# sa_amp.net
KiCad netlist of a schematic drawn in EAGLE
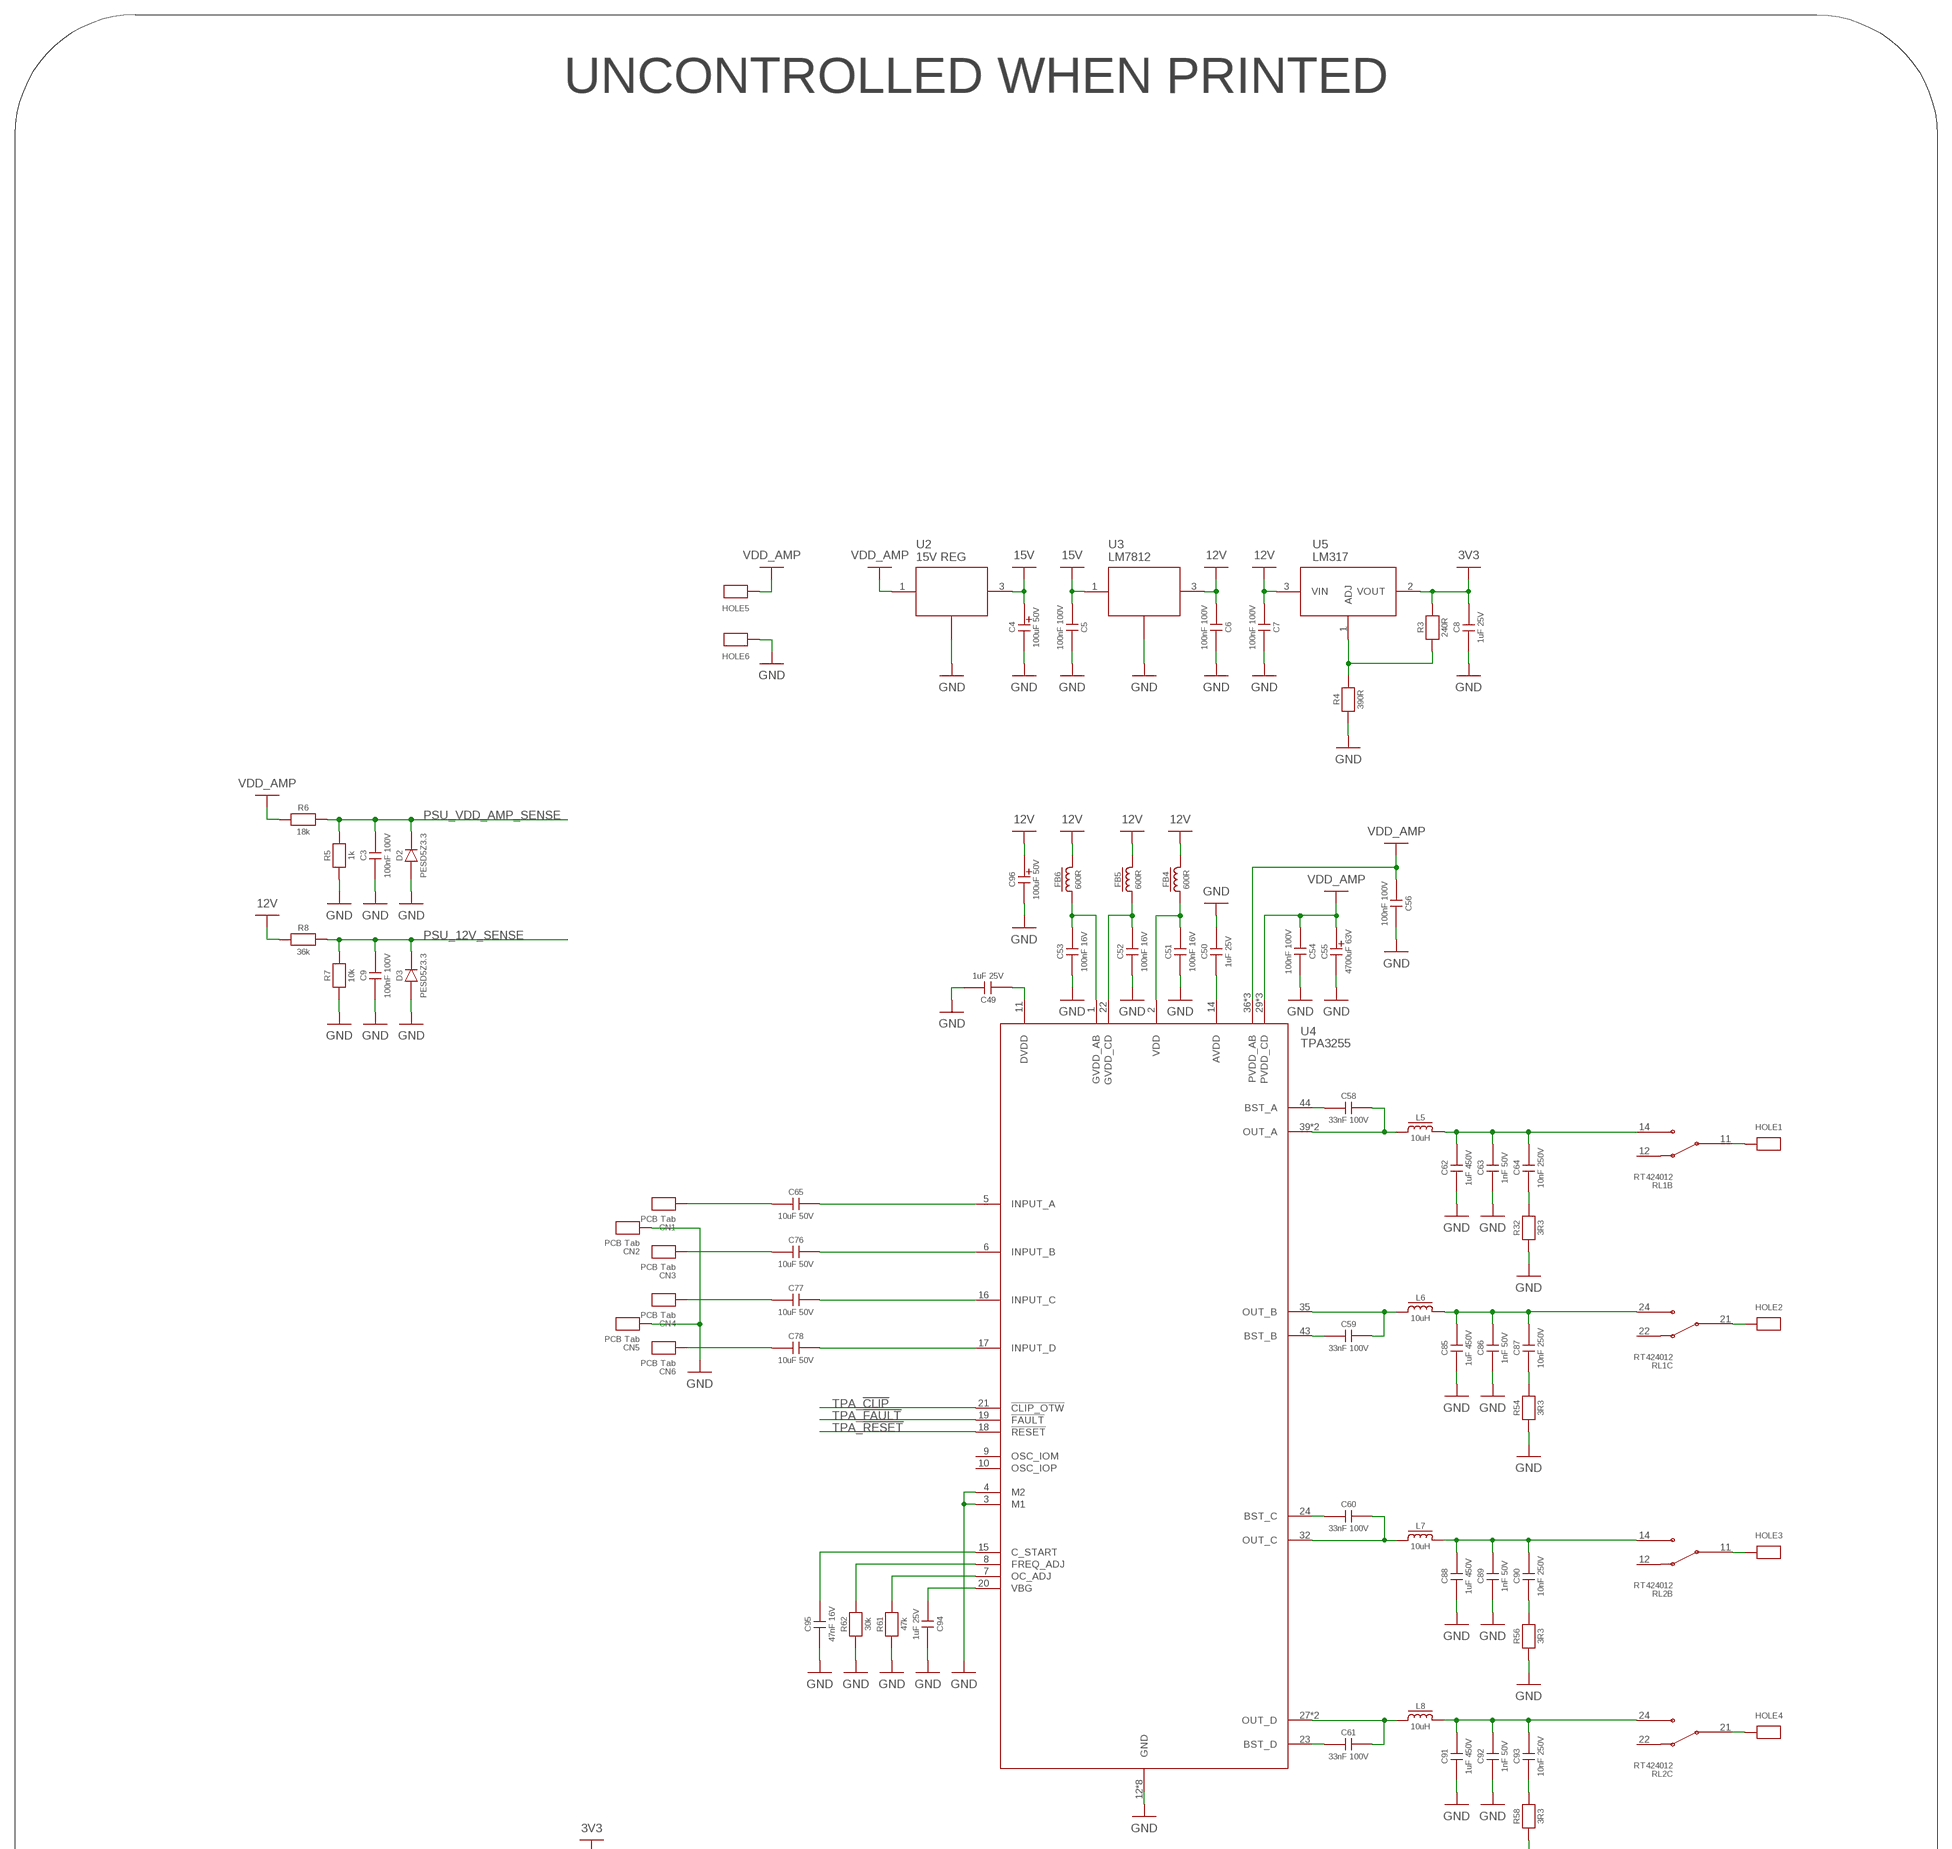
[diagram p0: schematic, sheet 1, part 1 of 2]
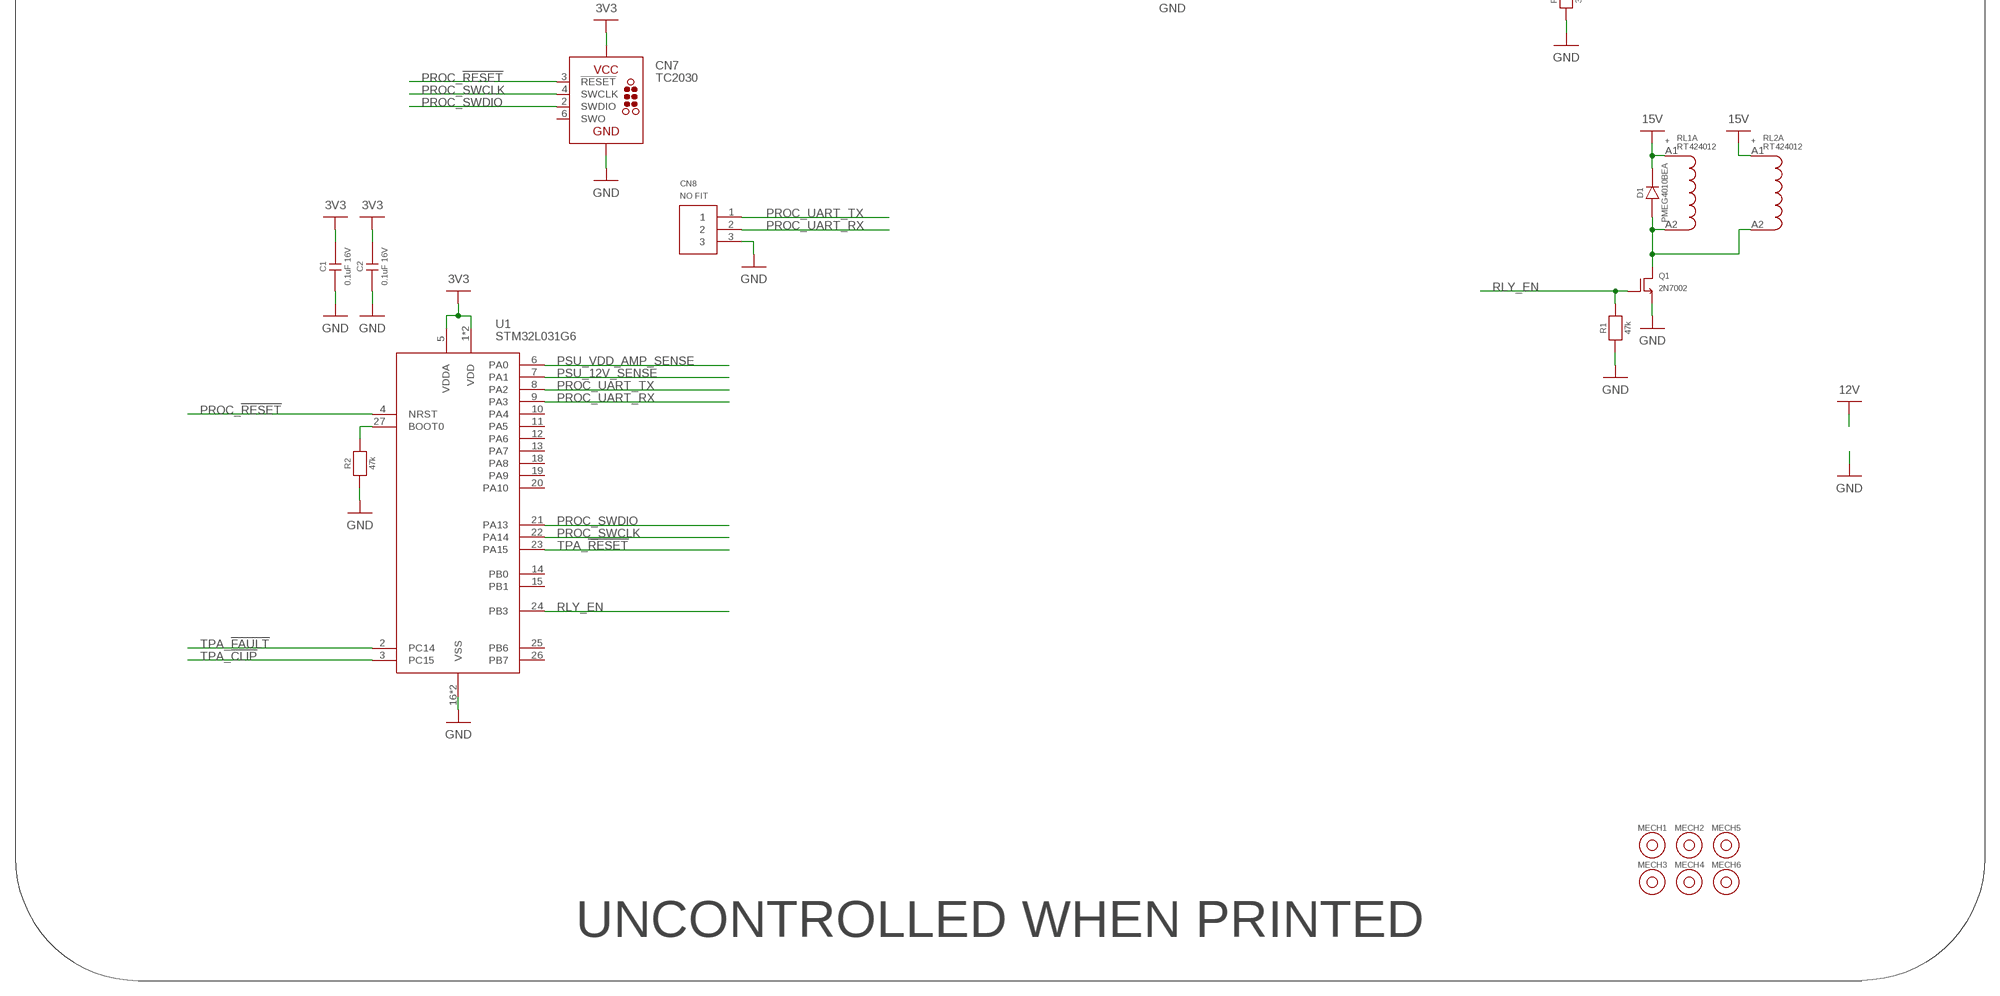
[diagram p1: schematic, sheet 1, part 2 of 2]

(export (version "E")
  (design (tool "Eeschema 10.0.6"))
  (components
    (comp (ref "C1")
      (value "0.1uF 16V")
      (footprint "eagle-import:0603")
      (fields
        (field (name "MANUFACTURER") "AVX Corporation")
        (field (name "TOLERANCE") "±10%")
        (field (name "VOLTAGE") "16V")
      )
      (libsource (lib "eagle-import") (part "0603YC104K4T4A"))
    )
    (comp (ref "C2")
      (value "0.1uF 16V")
      (footprint "eagle-import:0603")
      (fields
        (field (name "MANUFACTURER") "AVX Corporation")
        (field (name "TOLERANCE") "±10%")
        (field (name "VOLTAGE") "16V")
      )
      (libsource (lib "eagle-import") (part "0603YC104K4T4A"))
    )
    (comp (ref "C3")
      (value "100nF 100V")
      (footprint "eagle-import:0603")
      (libsource (lib "eagle-import") (part "06031C104KAT2A"))
    )
    (comp (ref "C4")
      (value "100uF 50V")
      (footprint "eagle-import:8MM_RADIAL_3.5MM_PITCH")
      (libsource (lib "eagle-import") (part "107CKR050M"))
    )
    (comp (ref "C5")
      (value "100nF 100V")
      (footprint "eagle-import:0603")
      (libsource (lib "eagle-import") (part "06031C104KAT2A"))
    )
    (comp (ref "C6")
      (value "100nF 100V")
      (footprint "eagle-import:0603")
      (libsource (lib "eagle-import") (part "06031C104KAT2A"))
    )
    (comp (ref "C7")
      (value "100nF 100V")
      (footprint "eagle-import:0603")
      (libsource (lib "eagle-import") (part "06031C104KAT2A"))
    )
    (comp (ref "C8")
      (value "1uF 25V")
      (footprint "eagle-import:0603")
      (libsource (lib "eagle-import") (part "CL10A105KA8NNNC"))
    )
    (comp (ref "C9")
      (value "100nF 100V")
      (footprint "eagle-import:0603")
      (libsource (lib "eagle-import") (part "06031C104KAT2A"))
    )
    (comp (ref "C49")
      (value "1uF 25V")
      (footprint "eagle-import:0603")
      (libsource (lib "eagle-import") (part "CL10A105KA8NNNC"))
    )
    (comp (ref "C50")
      (value "1uF 25V")
      (footprint "eagle-import:0603")
      (libsource (lib "eagle-import") (part "CL10A105KA8NNNC"))
    )
    (comp (ref "C51")
      (value "100nF 16V")
      (footprint "eagle-import:0603")
      (libsource (lib "eagle-import") (part "CL10B104KO8WPNC"))
    )
    (comp (ref "C52")
      (value "100nF 16V")
      (footprint "eagle-import:0603")
      (libsource (lib "eagle-import") (part "CL10B104KO8WPNC"))
    )
    (comp (ref "C53")
      (value "100nF 16V")
      (footprint "eagle-import:0603")
      (libsource (lib "eagle-import") (part "CL10B104KO8WPNC"))
    )
    (comp (ref "C54")
      (value "100nF 100V")
      (footprint "eagle-import:0603")
      (libsource (lib "eagle-import") (part "06031C104KAT2A"))
    )
    (comp (ref "C55")
      (value "4700uF 63V")
      (footprint "eagle-import:30MM_RADIAL_10MM_PITCH")
      (libsource (lib "eagle-import") (part "B41231C8478M000"))
    )
    (comp (ref "C56")
      (value "100nF 100V")
      (footprint "eagle-import:0603")
      (libsource (lib "eagle-import") (part "06031C104KAT2A"))
    )
    (comp (ref "C58")
      (value "33nF 100V")
      (footprint "eagle-import:0603")
      (libsource (lib "eagle-import") (part "C0603C333K1RACTU"))
    )
    (comp (ref "C59")
      (value "33nF 100V")
      (footprint "eagle-import:0603")
      (libsource (lib "eagle-import") (part "C0603C333K1RACTU"))
    )
    (comp (ref "C60")
      (value "33nF 100V")
      (footprint "eagle-import:0603")
      (libsource (lib "eagle-import") (part "C0603C333K1RACTU"))
    )
    (comp (ref "C61")
      (value "33nF 100V")
      (footprint "eagle-import:0603")
      (libsource (lib "eagle-import") (part "C0603C333K1RACTU"))
    )
    (comp (ref "C62")
      (value "1uF 450V")
      (footprint "eagle-import:7X17.5BOX")
      (libsource (lib "eagle-import") (part "ECWFE2W105K"))
    )
    (comp (ref "C63")
      (value "1nF 50V")
      (footprint "eagle-import:0603")
      (libsource (lib "eagle-import") (part "CL10B102KB8NNNC"))
    )
    (comp (ref "C64")
      (value "10nF 250V")
      (footprint "eagle-import:0603")
      (libsource (lib "eagle-import") (part "885342206006"))
    )
    (comp (ref "C65")
      (value "10uF 50V")
      (footprint "eagle-import:7.2X11BOX")
      (libsource (lib "eagle-import") (part "MKS2B051001N00JSSD"))
    )
    (comp (ref "C76")
      (value "10uF 50V")
      (footprint "eagle-import:7.2X11BOX")
      (libsource (lib "eagle-import") (part "MKS2B051001N00JSSD"))
    )
    (comp (ref "C77")
      (value "10uF 50V")
      (footprint "eagle-import:7.2X11BOX")
      (libsource (lib "eagle-import") (part "MKS2B051001N00JSSD"))
    )
    (comp (ref "C78")
      (value "10uF 50V")
      (footprint "eagle-import:7.2X11BOX")
      (libsource (lib "eagle-import") (part "MKS2B051001N00JSSD"))
    )
    (comp (ref "C85")
      (value "1uF 450V")
      (footprint "eagle-import:7X17.5BOX")
      (libsource (lib "eagle-import") (part "ECWFE2W105K"))
    )
    (comp (ref "C86")
      (value "1nF 50V")
      (footprint "eagle-import:0603")
      (libsource (lib "eagle-import") (part "CL10B102KB8NNNC"))
    )
    (comp (ref "C87")
      (value "10nF 250V")
      (footprint "eagle-import:0603")
      (libsource (lib "eagle-import") (part "885342206006"))
    )
    (comp (ref "C88")
      (value "1uF 450V")
      (footprint "eagle-import:7X17.5BOX")
      (libsource (lib "eagle-import") (part "ECWFE2W105K"))
    )
    (comp (ref "C89")
      (value "1nF 50V")
      (footprint "eagle-import:0603")
      (libsource (lib "eagle-import") (part "CL10B102KB8NNNC"))
    )
    (comp (ref "C90")
      (value "10nF 250V")
      (footprint "eagle-import:0603")
      (libsource (lib "eagle-import") (part "885342206006"))
    )
    (comp (ref "C91")
      (value "1uF 450V")
      (footprint "eagle-import:7X17.5BOX")
      (libsource (lib "eagle-import") (part "ECWFE2W105K"))
    )
    (comp (ref "C92")
      (value "1nF 50V")
      (footprint "eagle-import:0603")
      (libsource (lib "eagle-import") (part "CL10B102KB8NNNC"))
    )
    (comp (ref "C93")
      (value "10nF 250V")
      (footprint "eagle-import:0603")
      (libsource (lib "eagle-import") (part "885342206006"))
    )
    (comp (ref "C94")
      (value "1uF 25V")
      (footprint "eagle-import:0603")
      (libsource (lib "eagle-import") (part "CL10A105KA8NNNC"))
    )
    (comp (ref "C95")
      (value "47nF 16V")
      (footprint "eagle-import:0603")
      (libsource (lib "eagle-import") (part "CL10B473KO8NNNC"))
    )
    (comp (ref "C96")
      (value "100uF 50V")
      (footprint "eagle-import:8MM_RADIAL_3.5MM_PITCH")
      (libsource (lib "eagle-import") (part "107CKR050M"))
    )
    (comp (ref "CN1")
      (value "PCB Tab")
      (footprint "eagle-import:PCB_TAB_SMALL")
      (libsource (lib "eagle-import") (part "PCB_TAB_SMALL"))
    )
    (comp (ref "CN2")
      (value "PCB Tab")
      (footprint "eagle-import:PCB_TAB_SMALL")
      (libsource (lib "eagle-import") (part "PCB_TAB_SMALL"))
    )
    (comp (ref "CN3")
      (value "PCB Tab")
      (footprint "eagle-import:PCB_TAB_SMALL")
      (libsource (lib "eagle-import") (part "PCB_TAB_SMALL"))
    )
    (comp (ref "CN4")
      (value "PCB Tab")
      (footprint "eagle-import:PCB_TAB_SMALL")
      (libsource (lib "eagle-import") (part "PCB_TAB_SMALL"))
    )
    (comp (ref "CN5")
      (value "PCB Tab")
      (footprint "eagle-import:PCB_TAB_SMALL")
      (libsource (lib "eagle-import") (part "PCB_TAB_SMALL"))
    )
    (comp (ref "CN6")
      (value "PCB Tab")
      (footprint "eagle-import:PCB_TAB_SMALL")
      (libsource (lib "eagle-import") (part "PCB_TAB_SMALL"))
    )
    (comp (ref "CN7")
      (value "TC2030")
      (footprint "eagle-import:TC2030-MCP")
      (libsource (lib "eagle-import") (part "TC2030-MCP"))
    )
    (comp (ref "CN8")
      (value "NO FIT")
      (footprint "eagle-import:3PIN_HEADER")
      (libsource (lib "eagle-import") (part "1X3_HEADER"))
    )
    (comp (ref "D1")
      (value "PMEG4010BEA")
      (footprint "eagle-import:SOD-323")
      (libsource (lib "eagle-import") (part "PMEG4010BEA"))
    )
    (comp (ref "D2")
      (value "PESD5Z3.3")
      (footprint "eagle-import:SC-79")
      (libsource (lib "eagle-import") (part "PESD5Z3.3"))
    )
    (comp (ref "D3")
      (value "PESD5Z3.3")
      (footprint "eagle-import:SC-79")
      (libsource (lib "eagle-import") (part "PESD5Z3.3"))
    )
    (comp (ref "FB4")
      (value "600R")
      (footprint "eagle-import:0603")
      (libsource (lib "eagle-import") (part "742792651"))
    )
    (comp (ref "FB5")
      (value "600R")
      (footprint "eagle-import:0603")
      (libsource (lib "eagle-import") (part "742792651"))
    )
    (comp (ref "FB6")
      (value "600R")
      (footprint "eagle-import:0603")
      (libsource (lib "eagle-import") (part "742792651"))
    )
    (comp (ref "HOLE1")
      (value "PCB Tab")
      (footprint "eagle-import:PCB_TAB")
      (libsource (lib "eagle-import") (part "PCB_TAB"))
    )
    (comp (ref "HOLE2")
      (value "PCB Tab")
      (footprint "eagle-import:PCB_TAB")
      (libsource (lib "eagle-import") (part "PCB_TAB"))
    )
    (comp (ref "HOLE3")
      (value "PCB Tab")
      (footprint "eagle-import:PCB_TAB")
      (libsource (lib "eagle-import") (part "PCB_TAB"))
    )
    (comp (ref "HOLE4")
      (value "PCB Tab")
      (footprint "eagle-import:PCB_TAB")
      (libsource (lib "eagle-import") (part "PCB_TAB"))
    )
    (comp (ref "HOLE5")
      (value "PCB Tab")
      (footprint "eagle-import:PCB_TAB")
      (libsource (lib "eagle-import") (part "PCB_TAB"))
    )
    (comp (ref "HOLE6")
      (value "PCB Tab")
      (footprint "eagle-import:PCB_TAB")
      (libsource (lib "eagle-import") (part "PCB_TAB"))
    )
    (comp (ref "L5")
      (value "10uH")
      (footprint "eagle-import:SRP1265A")
      (libsource (lib "eagle-import") (part "SRP1265A-100M"))
    )
    (comp (ref "L6")
      (value "10uH")
      (footprint "eagle-import:SRP1265A")
      (libsource (lib "eagle-import") (part "SRP1265A-100M"))
    )
    (comp (ref "L7")
      (value "10uH")
      (footprint "eagle-import:SRP1265A")
      (libsource (lib "eagle-import") (part "SRP1265A-100M"))
    )
    (comp (ref "L8")
      (value "10uH")
      (footprint "eagle-import:SRP1265A")
      (libsource (lib "eagle-import") (part "SRP1265A-100M"))
    )
    (comp (ref "MECH1")
      (value "6mm x 3mm")
      (footprint "eagle-import:MOUNTHOLE_6X3")
      (libsource (lib "eagle-import") (part "MOUNTHOLE"))
    )
    (comp (ref "MECH2")
      (value "6mm x 3mm")
      (footprint "eagle-import:MOUNTHOLE_6X3")
      (libsource (lib "eagle-import") (part "MOUNTHOLE"))
    )
    (comp (ref "MECH3")
      (value "6mm x 3mm")
      (footprint "eagle-import:MOUNTHOLE_6X3")
      (libsource (lib "eagle-import") (part "MOUNTHOLE"))
    )
    (comp (ref "MECH4")
      (value "6mm x 3mm")
      (footprint "eagle-import:MOUNTHOLE_6X3")
      (libsource (lib "eagle-import") (part "MOUNTHOLE"))
    )
    (comp (ref "MECH5")
      (value "6mm x 3mm")
      (footprint "eagle-import:MOUNTHOLE_6X3")
      (libsource (lib "eagle-import") (part "MOUNTHOLE"))
    )
    (comp (ref "MECH6")
      (value "6mm x 3mm")
      (footprint "eagle-import:MOUNTHOLE_6X3")
      (libsource (lib "eagle-import") (part "MOUNTHOLE"))
    )
    (comp (ref "Q1")
      (value "2N7002")
      (footprint "eagle-import:SOT23-3")
      (libsource (lib "eagle-import") (part "2N7002P,215"))
    )
    (comp (ref "R1")
      (value "47k")
      (footprint "eagle-import:0603")
      (libsource (lib "eagle-import") (part "ERJ3EKF4702V"))
    )
    (comp (ref "R2")
      (value "47k")
      (footprint "eagle-import:0603")
      (libsource (lib "eagle-import") (part "ERJ3EKF4702V"))
    )
    (comp (ref "R3")
      (value "240R")
      (footprint "eagle-import:0603")
      (fields
        (field (name "MANUFACTURER") "Vishay Dale")
        (field (name "POWER") "0.1W, 1/10W")
        (field (name "TOLERANCE") "±1%")
      )
      (libsource (lib "eagle-import") (part "CRCW0603240RFKEA"))
    )
    (comp (ref "R4")
      (value "390R")
      (footprint "eagle-import:0603")
      (fields
        (field (name "MANUFACTURER") "Vishay Dale")
        (field (name "POWER") "0.1W, 1/10W")
        (field (name "TOLERANCE") "±1%")
      )
      (libsource (lib "eagle-import") (part "CRCW0603390RFKEA"))
    )
    (comp (ref "R5")
      (value "1k")
      (footprint "eagle-import:0603")
      (fields
        (field (name "MANUFACTURER") "Vishay Dale")
        (field (name "POWER") "0.1W, 1/10W")
        (field (name "TOLERANCE") "±1%")
      )
      (libsource (lib "eagle-import") (part "CRCW06031K00FKEB"))
    )
    (comp (ref "R6")
      (value "18k")
      (footprint "eagle-import:0603")
      (fields
        (field (name "MANUFACTURER") "Vishay Dale")
        (field (name "POWER") "0.1W, 1/10W")
        (field (name "TOLERANCE") "±1%")
      )
      (libsource (lib "eagle-import") (part "CRCW060318K0FKEA"))
    )
    (comp (ref "R7")
      (value "10k")
      (footprint "eagle-import:0603")
      (fields
        (field (name "MANUFACTURER") "Vishay Dale")
        (field (name "POWER") "0.1W, 1/10W")
        (field (name "TOLERANCE") "±1%")
      )
      (libsource (lib "eagle-import") (part "CRCW060310K0FKTA"))
    )
    (comp (ref "R8")
      (value "36k")
      (footprint "eagle-import:0603")
      (fields
        (field (name "MANUFACTURER") "Vishay Dale")
        (field (name "POWER") "0.1W, 1/10W")
        (field (name "TOLERANCE") "±1%")
      )
      (libsource (lib "eagle-import") (part "CRCW060336K0FKEA"))
    )
    (comp (ref "R32")
      (value "3R3")
      (footprint "eagle-import:2512")
      (libsource (lib "eagle-import") (part "RL73H3AR10FTDF"))
    )
    (comp (ref "R54")
      (value "3R3")
      (footprint "eagle-import:2512")
      (libsource (lib "eagle-import") (part "RL73H3AR10FTDF"))
    )
    (comp (ref "R56")
      (value "3R3")
      (footprint "eagle-import:2512")
      (libsource (lib "eagle-import") (part "RL73H3AR10FTDF"))
    )
    (comp (ref "R58")
      (value "3R3")
      (footprint "eagle-import:2512")
      (libsource (lib "eagle-import") (part "RL73H3AR10FTDF"))
    )
    (comp (ref "R61")
      (value "47k")
      (footprint "eagle-import:0603")
      (libsource (lib "eagle-import") (part "ERJ3EKF4702V"))
    )
    (comp (ref "R62")
      (value "30k")
      (footprint "eagle-import:0603")
      (libsource (lib "eagle-import") (part "ERJ3EKF3002V"))
    )
    (comp (ref "RL1")
      (value "RT424012")
      (footprint "eagle-import:30MMDPDTRELAY")
      (libsource (lib "eagle-import") (part "RT424012"))
    )
    (comp (ref "RL2")
      (value "RT424012")
      (footprint "eagle-import:30MMDPDTRELAY")
      (libsource (lib "eagle-import") (part "RT424012"))
    )
    (comp (ref "U1")
      (value "STM32L031G6")
      (footprint "eagle-import:UFQPN28")
      (libsource (lib "eagle-import") (part "STM32L031G6"))
    )
    (comp (ref "U2")
      (value "15V REG")
      (footprint "eagle-import:SRH05")
      (libsource (lib "eagle-import") (part "SRH05S15"))
    )
    (comp (ref "U3")
      (value "LM7812")
      (footprint "eagle-import:TO220")
      (libsource (lib "eagle-import") (part "78CTG12"))
    )
    (comp (ref "U4")
      (value "TPA3255")
      (footprint "eagle-import:HTSSOP44")
      (libsource (lib "eagle-import") (part "TPA3255"))
    )
    (comp (ref "U5")
      (value "LM317")
      (footprint "eagle-import:SOT89")
      (libsource (lib "eagle-import") (part "LM317LCPK"))
    )
  )
  (nets
    (net (code "1") (name "/PROC_SWCLK") (class "Default")
      (node (ref "CN7") (pin "4") (pinfunction "SWCLK_4") (pintype "power_in"))
      (node (ref "U1") (pin "22") (pinfunction "PA14_22") (pintype "bidirectional"))
    )
    (net (code "2") (name "/PROC_SWDIO") (class "Default")
      (node (ref "CN7") (pin "2") (pinfunction "SWDIO_2") (pintype "bidirectional"))
      (node (ref "U1") (pin "21") (pinfunction "PA13_21") (pintype "bidirectional"))
    )
    (net (code "3") (name "/PROC_UART_RX") (class "Default")
      (node (ref "CN8") (pin "2") (pinfunction "2_2") (pintype "bidirectional"))
      (node (ref "U1") (pin "9") (pinfunction "PA3_9") (pintype "bidirectional"))
    )
    (net (code "4") (name "/PROC_UART_TX") (class "Default")
      (node (ref "CN8") (pin "1") (pinfunction "1_1") (pintype "bidirectional"))
      (node (ref "U1") (pin "8") (pinfunction "PA2_8") (pintype "bidirectional"))
    )
    (net (code "5") (name "/PROC_~{RESET}") (class "Default")
      (node (ref "CN7") (pin "3") (pinfunction "~{RESET}_3") (pintype "power_in"))
      (node (ref "U1") (pin "4") (pinfunction "NRST_4") (pintype "bidirectional"))
    )
    (net (code "6") (name "/PSU_12V_SENSE") (class "Default")
      (node (ref "C9") (pin "1") (pinfunction "1_1") (pintype "bidirectional"))
      (node (ref "D3") (pin "K") (pinfunction "K_K") (pintype "bidirectional"))
      (node (ref "R7") (pin "2") (pinfunction "2_2") (pintype "bidirectional"))
      (node (ref "R8") (pin "2") (pinfunction "2_2") (pintype "bidirectional"))
      (node (ref "U1") (pin "7") (pinfunction "PA1_7") (pintype "bidirectional"))
    )
    (net (code "7") (name "/PSU_VDD_AMP_SENSE") (class "Default")
      (node (ref "C3") (pin "1") (pinfunction "1_1") (pintype "bidirectional"))
      (node (ref "D2") (pin "K") (pinfunction "K_K") (pintype "bidirectional"))
      (node (ref "R5") (pin "2") (pinfunction "2_2") (pintype "bidirectional"))
      (node (ref "R6") (pin "2") (pinfunction "2_2") (pintype "bidirectional"))
      (node (ref "U1") (pin "6") (pinfunction "PA0_6") (pintype "bidirectional"))
    )
    (net (code "8") (name "/RLY_EN") (class "Default")
      (node (ref "Q1") (pin "1") (pinfunction "G_1") (pintype "bidirectional"))
      (node (ref "R1") (pin "2") (pinfunction "2_2") (pintype "bidirectional"))
      (node (ref "U1") (pin "24") (pinfunction "PB3_24") (pintype "bidirectional"))
    )
    (net (code "9") (name "/TPA_~{CLIP}") (class "Default")
      (node (ref "U1") (pin "3") (pinfunction "PC15_3") (pintype "bidirectional"))
      (node (ref "U4") (pin "21") (pinfunction "~{CLIP_OTW}_21") (pintype "bidirectional"))
    )
    (net (code "10") (name "/TPA_~{FAULT}") (class "Default")
      (node (ref "U1") (pin "2") (pinfunction "PC14_2") (pintype "bidirectional"))
      (node (ref "U4") (pin "19") (pinfunction "~{FAULT}_19") (pintype "bidirectional"))
    )
    (net (code "11") (name "/TPA_~{RESET}") (class "Default")
      (node (ref "U1") (pin "23") (pinfunction "PA15_23") (pintype "bidirectional"))
      (node (ref "U4") (pin "18") (pinfunction "~{RESET}_18") (pintype "bidirectional"))
    )
    (net (code "12") (name "3V3") (class "Default")
      (node (ref "C1") (pin "2") (pinfunction "2_2") (pintype "bidirectional"))
      (node (ref "C2") (pin "2") (pinfunction "2_2") (pintype "bidirectional"))
      (node (ref "C8") (pin "2") (pinfunction "2_2") (pintype "bidirectional"))
      (node (ref "CN7") (pin "1") (pinfunction "VCC_1") (pintype "passive"))
      (node (ref "R3") (pin "2") (pinfunction "2_2") (pintype "bidirectional"))
      (node (ref "U1") (pin "1") (pinfunction "VDD_1") (pintype "bidirectional"))
      (node (ref "U1") (pin "17") (pinfunction "VDD_17") (pintype "bidirectional"))
      (node (ref "U1") (pin "5") (pinfunction "VDDA_5") (pintype "bidirectional"))
      (node (ref "U5") (pin "2") (pinfunction "VOUT_2") (pintype "bidirectional"))
    )
    (net (code "13") (name "12V") (class "Default")
      (node (ref "C6") (pin "1") (pinfunction "1_1") (pintype "bidirectional"))
      (node (ref "C7") (pin "1") (pinfunction "1_1") (pintype "bidirectional"))
      (node (ref "C96") (pin "P") (pinfunction "A_P") (pintype "bidirectional"))
      (node (ref "FB4") (pin "2") (pinfunction "2_2") (pintype "bidirectional"))
      (node (ref "FB5") (pin "2") (pinfunction "2_2") (pintype "bidirectional"))
      (node (ref "FB6") (pin "2") (pinfunction "2_2") (pintype "bidirectional"))
      (node (ref "R8") (pin "1") (pinfunction "1_1") (pintype "bidirectional"))
      (node (ref "U3") (pin "3") (pinfunction "VOUT_3") (pintype "bidirectional"))
      (node (ref "U5") (pin "3") (pinfunction "VIN_3") (pintype "bidirectional"))
    )
    (net (code "14") (name "15V") (class "Default")
      (node (ref "C4") (pin "P") (pinfunction "A_P") (pintype "bidirectional"))
      (node (ref "C5") (pin "1") (pinfunction "1_1") (pintype "bidirectional"))
      (node (ref "D1") (pin "K") (pinfunction "K_K") (pintype "bidirectional"))
      (node (ref "RL1") (pin "A1") (pinfunction "A1_A1") (pintype "bidirectional"))
      (node (ref "RL2") (pin "A1") (pinfunction "A1_A1") (pintype "bidirectional"))
      (node (ref "U2") (pin "3") (pinfunction "VOUT_3") (pintype "bidirectional"))
      (node (ref "U3") (pin "1") (pinfunction "VIN_1") (pintype "bidirectional"))
    )
    (net (code "15") (name "GND") (class "Default")
      (node (ref "C1") (pin "1") (pinfunction "1_1") (pintype "bidirectional"))
      (node (ref "C2") (pin "1") (pinfunction "1_1") (pintype "bidirectional"))
      (node (ref "C3") (pin "2") (pinfunction "2_2") (pintype "bidirectional"))
      (node (ref "C4") (pin "N") (pinfunction "K_N") (pintype "bidirectional"))
      (node (ref "C49") (pin "2") (pinfunction "2_2") (pintype "bidirectional"))
      (node (ref "C5") (pin "2") (pinfunction "2_2") (pintype "bidirectional"))
      (node (ref "C50") (pin "2") (pinfunction "2_2") (pintype "bidirectional"))
      (node (ref "C51") (pin "1") (pinfunction "1_1") (pintype "bidirectional"))
      (node (ref "C52") (pin "1") (pinfunction "1_1") (pintype "bidirectional"))
      (node (ref "C53") (pin "1") (pinfunction "1_1") (pintype "bidirectional"))
      (node (ref "C54") (pin "2") (pinfunction "2_2") (pintype "bidirectional"))
      (node (ref "C55") (pin "1") (pinfunction "K_1") (pintype "bidirectional"))
      (node (ref "C56") (pin "2") (pinfunction "2_2") (pintype "bidirectional"))
      (node (ref "C6") (pin "2") (pinfunction "2_2") (pintype "bidirectional"))
      (node (ref "C62") (pin "1") (pinfunction "1_1") (pintype "bidirectional"))
      (node (ref "C63") (pin "1") (pinfunction "1_1") (pintype "bidirectional"))
      (node (ref "C7") (pin "2") (pinfunction "2_2") (pintype "bidirectional"))
      (node (ref "C8") (pin "1") (pinfunction "1_1") (pintype "bidirectional"))
      (node (ref "C85") (pin "1") (pinfunction "1_1") (pintype "bidirectional"))
      (node (ref "C86") (pin "1") (pinfunction "1_1") (pintype "bidirectional"))
      (node (ref "C88") (pin "1") (pinfunction "1_1") (pintype "bidirectional"))
      (node (ref "C89") (pin "1") (pinfunction "1_1") (pintype "bidirectional"))
      (node (ref "C9") (pin "2") (pinfunction "2_2") (pintype "bidirectional"))
      (node (ref "C91") (pin "1") (pinfunction "1_1") (pintype "bidirectional"))
      (node (ref "C92") (pin "1") (pinfunction "1_1") (pintype "bidirectional"))
      (node (ref "C94") (pin "2") (pinfunction "2_2") (pintype "bidirectional"))
      (node (ref "C95") (pin "1") (pinfunction "1_1") (pintype "bidirectional"))
      (node (ref "C96") (pin "N") (pinfunction "K_N") (pintype "bidirectional"))
      (node (ref "CN2") (pin "1") (pinfunction "1_1") (pintype "bidirectional"))
      (node (ref "CN5") (pin "1") (pinfunction "1_1") (pintype "bidirectional"))
      (node (ref "CN7") (pin "5") (pinfunction "GND_5") (pintype "bidirectional"))
      (node (ref "CN8") (pin "3") (pinfunction "3_3") (pintype "bidirectional"))
      (node (ref "D2") (pin "A") (pinfunction "A_A") (pintype "bidirectional"))
      (node (ref "D3") (pin "A") (pinfunction "A_A") (pintype "bidirectional"))
      (node (ref "HOLE6") (pin "1") (pinfunction "1_1") (pintype "bidirectional"))
      (node (ref "Q1") (pin "3") (pinfunction "S_3") (pintype "bidirectional"))
      (node (ref "R1") (pin "1") (pinfunction "1_1") (pintype "bidirectional"))
      (node (ref "R2") (pin "1") (pinfunction "1_1") (pintype "bidirectional"))
      (node (ref "R32") (pin "1") (pinfunction "1_1") (pintype "bidirectional"))
      (node (ref "R4") (pin "1") (pinfunction "1_1") (pintype "bidirectional"))
      (node (ref "R5") (pin "1") (pinfunction "1_1") (pintype "bidirectional"))
      (node (ref "R54") (pin "1") (pinfunction "1_1") (pintype "bidirectional"))
      (node (ref "R56") (pin "1") (pinfunction "1_1") (pintype "bidirectional"))
      (node (ref "R58") (pin "1") (pinfunction "1_1") (pintype "bidirectional"))
      (node (ref "R61") (pin "1") (pinfunction "1_1") (pintype "bidirectional"))
      (node (ref "R62") (pin "1") (pinfunction "1_1") (pintype "bidirectional"))
      (node (ref "R7") (pin "1") (pinfunction "1_1") (pintype "bidirectional"))
      (node (ref "U1") (pin "16") (pinfunction "VSS_16") (pintype "bidirectional"))
      (node (ref "U1") (pin "28") (pinfunction "VSS_28") (pintype "bidirectional"))
      (node (ref "U2") (pin "2") (pinfunction "GND_2") (pintype "bidirectional"))
      (node (ref "U3") (pin "2") (pinfunction "GND_2") (pintype "bidirectional"))
      (node (ref "U4") (pin "12") (pinfunction "GND_12") (pintype "bidirectional"))
      (node (ref "U4") (pin "13") (pinfunction "GND_13") (pintype "bidirectional"))
      (node (ref "U4") (pin "25") (pinfunction "GND_25") (pintype "bidirectional"))
      (node (ref "U4") (pin "26") (pinfunction "GND_26") (pintype "bidirectional"))
      (node (ref "U4") (pin "3") (pinfunction "M1_3") (pintype "bidirectional"))
      (node (ref "U4") (pin "33") (pinfunction "GND_33") (pintype "bidirectional"))
      (node (ref "U4") (pin "34") (pinfunction "GND_34") (pintype "bidirectional"))
      (node (ref "U4") (pin "4") (pinfunction "M2_4") (pintype "bidirectional"))
      (node (ref "U4") (pin "41") (pinfunction "GND_41") (pintype "bidirectional"))
      (node (ref "U4") (pin "42") (pinfunction "GND_42") (pintype "bidirectional"))
    )
    (net (code "16") (name "Net-(C58-Pad2)") (class "Default")
      (node (ref "C58") (pin "2") (pinfunction "2_2") (pintype "bidirectional"))
      (node (ref "L5") (pin "1") (pinfunction "1_1") (pintype "bidirectional"))
      (node (ref "U4") (pin "39") (pinfunction "OUT_A_39") (pintype "bidirectional"))
      (node (ref "U4") (pin "40") (pinfunction "OUT_A_40") (pintype "bidirectional"))
    )
    (net (code "17") (name "Net-(C61-Pad2)") (class "Default")
      (node (ref "C61") (pin "2") (pinfunction "2_2") (pintype "bidirectional"))
      (node (ref "L8") (pin "1") (pinfunction "1_1") (pintype "bidirectional"))
      (node (ref "U4") (pin "27") (pinfunction "OUT_D_27") (pintype "bidirectional"))
      (node (ref "U4") (pin "28") (pinfunction "OUT_D_28") (pintype "bidirectional"))
    )
    (net (code "18") (name "Net-(C64-Pad1)") (class "Default")
      (node (ref "C64") (pin "1") (pinfunction "1_1") (pintype "bidirectional"))
      (node (ref "R32") (pin "2") (pinfunction "2_2") (pintype "bidirectional"))
    )
    (net (code "19") (name "Net-(C65-Pad1)") (class "Default")
      (node (ref "C65") (pin "1") (pinfunction "1_1") (pintype "bidirectional"))
      (node (ref "CN1") (pin "1") (pinfunction "1_1") (pintype "bidirectional"))
    )
    (net (code "20") (name "Net-(C76-Pad1)") (class "Default")
      (node (ref "C76") (pin "1") (pinfunction "1_1") (pintype "bidirectional"))
      (node (ref "CN3") (pin "1") (pinfunction "1_1") (pintype "bidirectional"))
    )
    (net (code "21") (name "Net-(C77-Pad1)") (class "Default")
      (node (ref "C77") (pin "1") (pinfunction "1_1") (pintype "bidirectional"))
      (node (ref "CN4") (pin "1") (pinfunction "1_1") (pintype "bidirectional"))
    )
    (net (code "22") (name "Net-(C78-Pad1)") (class "Default")
      (node (ref "C78") (pin "1") (pinfunction "1_1") (pintype "bidirectional"))
      (node (ref "CN6") (pin "1") (pinfunction "1_1") (pintype "bidirectional"))
    )
    (net (code "23") (name "Net-(C87-Pad1)") (class "Default")
      (node (ref "C87") (pin "1") (pinfunction "1_1") (pintype "bidirectional"))
      (node (ref "R54") (pin "2") (pinfunction "2_2") (pintype "bidirectional"))
    )
    (net (code "24") (name "Net-(C90-Pad1)") (class "Default")
      (node (ref "C90") (pin "1") (pinfunction "1_1") (pintype "bidirectional"))
      (node (ref "R56") (pin "2") (pinfunction "2_2") (pintype "bidirectional"))
    )
    (net (code "25") (name "Net-(C93-Pad1)") (class "Default")
      (node (ref "C93") (pin "1") (pinfunction "1_1") (pintype "bidirectional"))
      (node (ref "R58") (pin "2") (pinfunction "2_2") (pintype "bidirectional"))
    )
    (net (code "26") (name "Net-(Q1-D)") (class "Default")
      (node (ref "D1") (pin "A") (pinfunction "A_A") (pintype "bidirectional"))
      (node (ref "Q1") (pin "2") (pinfunction "D_2") (pintype "bidirectional"))
      (node (ref "RL1") (pin "A2") (pinfunction "A2_A2") (pintype "bidirectional"))
      (node (ref "RL2") (pin "A2") (pinfunction "A2_A2") (pintype "bidirectional"))
    )
    (net (code "27") (name "Net-(RL1B-1)") (class "Default")
      (node (ref "HOLE1") (pin "1") (pinfunction "1_1") (pintype "bidirectional"))
      (node (ref "RL1") (pin "11") (pinfunction "1_11") (pintype "bidirectional"))
    )
    (net (code "28") (name "Net-(RL1B-3)") (class "Default")
      (node (ref "C62") (pin "2") (pinfunction "2_2") (pintype "bidirectional"))
      (node (ref "C63") (pin "2") (pinfunction "2_2") (pintype "bidirectional"))
      (node (ref "C64") (pin "2") (pinfunction "2_2") (pintype "bidirectional"))
      (node (ref "L5") (pin "2") (pinfunction "2_2") (pintype "bidirectional"))
      (node (ref "RL1") (pin "14") (pinfunction "3_14") (pintype "bidirectional"))
    )
    (net (code "29") (name "Net-(RL1C-1)") (class "Default")
      (node (ref "HOLE2") (pin "1") (pinfunction "1_1") (pintype "bidirectional"))
      (node (ref "RL1") (pin "21") (pinfunction "1_21") (pintype "bidirectional"))
    )
    (net (code "30") (name "Net-(RL1C-3)") (class "Default")
      (node (ref "C85") (pin "2") (pinfunction "2_2") (pintype "bidirectional"))
      (node (ref "C86") (pin "2") (pinfunction "2_2") (pintype "bidirectional"))
      (node (ref "C87") (pin "2") (pinfunction "2_2") (pintype "bidirectional"))
      (node (ref "L6") (pin "2") (pinfunction "2_2") (pintype "bidirectional"))
      (node (ref "RL1") (pin "24") (pinfunction "3_24") (pintype "bidirectional"))
    )
    (net (code "31") (name "Net-(RL2B-1)") (class "Default")
      (node (ref "HOLE3") (pin "1") (pinfunction "1_1") (pintype "bidirectional"))
      (node (ref "RL2") (pin "11") (pinfunction "1_11") (pintype "bidirectional"))
    )
    (net (code "32") (name "Net-(RL2B-3)") (class "Default")
      (node (ref "C88") (pin "2") (pinfunction "2_2") (pintype "bidirectional"))
      (node (ref "C89") (pin "2") (pinfunction "2_2") (pintype "bidirectional"))
      (node (ref "C90") (pin "2") (pinfunction "2_2") (pintype "bidirectional"))
      (node (ref "L7") (pin "2") (pinfunction "2_2") (pintype "bidirectional"))
      (node (ref "RL2") (pin "14") (pinfunction "3_14") (pintype "bidirectional"))
    )
    (net (code "33") (name "Net-(RL2C-1)") (class "Default")
      (node (ref "HOLE4") (pin "1") (pinfunction "1_1") (pintype "bidirectional"))
      (node (ref "RL2") (pin "21") (pinfunction "1_21") (pintype "bidirectional"))
    )
    (net (code "34") (name "Net-(RL2C-3)") (class "Default")
      (node (ref "C91") (pin "2") (pinfunction "2_2") (pintype "bidirectional"))
      (node (ref "C92") (pin "2") (pinfunction "2_2") (pintype "bidirectional"))
      (node (ref "C93") (pin "2") (pinfunction "2_2") (pintype "bidirectional"))
      (node (ref "L8") (pin "2") (pinfunction "2_2") (pintype "bidirectional"))
      (node (ref "RL2") (pin "24") (pinfunction "3_24") (pintype "bidirectional"))
    )
    (net (code "35") (name "Net-(U1-BOOT0)") (class "Default")
      (node (ref "R2") (pin "2") (pinfunction "2_2") (pintype "bidirectional"))
      (node (ref "U1") (pin "27") (pinfunction "BOOT0_27") (pintype "bidirectional"))
    )
    (net (code "36") (name "Net-(U4-AVDD)") (class "Default")
      (node (ref "C50") (pin "1") (pinfunction "1_1") (pintype "bidirectional"))
      (node (ref "U4") (pin "14") (pinfunction "AVDD_14") (pintype "bidirectional"))
    )
    (net (code "37") (name "Net-(U4-BST_A)") (class "Default")
      (node (ref "C58") (pin "1") (pinfunction "1_1") (pintype "bidirectional"))
      (node (ref "U4") (pin "44") (pinfunction "BST_A_44") (pintype "bidirectional"))
    )
    (net (code "38") (name "Net-(U4-BST_B)") (class "Default")
      (node (ref "C59") (pin "1") (pinfunction "1_1") (pintype "bidirectional"))
      (node (ref "U4") (pin "43") (pinfunction "BST_B_43") (pintype "bidirectional"))
    )
    (net (code "39") (name "Net-(U4-BST_C)") (class "Default")
      (node (ref "C60") (pin "1") (pinfunction "1_1") (pintype "bidirectional"))
      (node (ref "U4") (pin "24") (pinfunction "BST_C_24") (pintype "bidirectional"))
    )
    (net (code "40") (name "Net-(U4-BST_D)") (class "Default")
      (node (ref "C61") (pin "1") (pinfunction "1_1") (pintype "bidirectional"))
      (node (ref "U4") (pin "23") (pinfunction "BST_D_23") (pintype "bidirectional"))
    )
    (net (code "41") (name "Net-(U4-C_START)") (class "Default")
      (node (ref "C95") (pin "2") (pinfunction "2_2") (pintype "bidirectional"))
      (node (ref "U4") (pin "15") (pinfunction "C_START_15") (pintype "bidirectional"))
    )
    (net (code "42") (name "Net-(U4-DVDD)") (class "Default")
      (node (ref "C49") (pin "1") (pinfunction "1_1") (pintype "bidirectional"))
      (node (ref "U4") (pin "11") (pinfunction "DVDD_11") (pintype "bidirectional"))
    )
    (net (code "43") (name "Net-(U4-FREQ_ADJ)") (class "Default")
      (node (ref "R62") (pin "2") (pinfunction "2_2") (pintype "bidirectional"))
      (node (ref "U4") (pin "8") (pinfunction "FREQ_ADJ_8") (pintype "bidirectional"))
    )
    (net (code "44") (name "Net-(U4-GVDD_AB)") (class "Default")
      (node (ref "C53") (pin "2") (pinfunction "2_2") (pintype "bidirectional"))
      (node (ref "FB6") (pin "1") (pinfunction "1_1") (pintype "bidirectional"))
      (node (ref "U4") (pin "1") (pinfunction "GVDD_AB_1") (pintype "bidirectional"))
    )
    (net (code "45") (name "Net-(U4-GVDD_CD)") (class "Default")
      (node (ref "C52") (pin "2") (pinfunction "2_2") (pintype "bidirectional"))
      (node (ref "FB5") (pin "1") (pinfunction "1_1") (pintype "bidirectional"))
      (node (ref "U4") (pin "22") (pinfunction "GVDD_CD_22") (pintype "bidirectional"))
    )
    (net (code "46") (name "Net-(U4-INPUT_A)") (class "Default")
      (node (ref "C65") (pin "2") (pinfunction "2_2") (pintype "bidirectional"))
      (node (ref "U4") (pin "5") (pinfunction "INPUT_A_5") (pintype "bidirectional"))
    )
    (net (code "47") (name "Net-(U4-INPUT_B)") (class "Default")
      (node (ref "C76") (pin "2") (pinfunction "2_2") (pintype "bidirectional"))
      (node (ref "U4") (pin "6") (pinfunction "INPUT_B_6") (pintype "bidirectional"))
    )
    (net (code "48") (name "Net-(U4-INPUT_C)") (class "Default")
      (node (ref "C77") (pin "2") (pinfunction "2_2") (pintype "bidirectional"))
      (node (ref "U4") (pin "16") (pinfunction "INPUT_C_16") (pintype "bidirectional"))
    )
    (net (code "49") (name "Net-(U4-INPUT_D)") (class "Default")
      (node (ref "C78") (pin "2") (pinfunction "2_2") (pintype "bidirectional"))
      (node (ref "U4") (pin "17") (pinfunction "INPUT_D_17") (pintype "bidirectional"))
    )
    (net (code "50") (name "Net-(U4-OC_ADJ)") (class "Default")
      (node (ref "R61") (pin "2") (pinfunction "2_2") (pintype "bidirectional"))
      (node (ref "U4") (pin "7") (pinfunction "OC_ADJ_7") (pintype "bidirectional"))
    )
    (net (code "51") (name "Net-(U4-OUT_B)") (class "Default")
      (node (ref "C59") (pin "2") (pinfunction "2_2") (pintype "bidirectional"))
      (node (ref "L6") (pin "1") (pinfunction "1_1") (pintype "bidirectional"))
      (node (ref "U4") (pin "35") (pinfunction "OUT_B_35") (pintype "bidirectional"))
    )
    (net (code "52") (name "Net-(U4-OUT_C)") (class "Default")
      (node (ref "C60") (pin "2") (pinfunction "2_2") (pintype "bidirectional"))
      (node (ref "L7") (pin "1") (pinfunction "1_1") (pintype "bidirectional"))
      (node (ref "U4") (pin "32") (pinfunction "OUT_C_32") (pintype "bidirectional"))
    )
    (net (code "53") (name "Net-(U4-VBG)") (class "Default")
      (node (ref "C94") (pin "1") (pinfunction "1_1") (pintype "bidirectional"))
      (node (ref "U4") (pin "20") (pinfunction "VBG_20") (pintype "bidirectional"))
    )
    (net (code "54") (name "Net-(U4-VDD)") (class "Default")
      (node (ref "C51") (pin "2") (pinfunction "2_2") (pintype "bidirectional"))
      (node (ref "FB4") (pin "1") (pinfunction "1_1") (pintype "bidirectional"))
      (node (ref "U4") (pin "2") (pinfunction "VDD_2") (pintype "bidirectional"))
    )
    (net (code "55") (name "Net-(U5-ADJ)") (class "Default")
      (node (ref "R3") (pin "1") (pinfunction "1_1") (pintype "bidirectional"))
      (node (ref "R4") (pin "2") (pinfunction "2_2") (pintype "bidirectional"))
      (node (ref "U5") (pin "1") (pinfunction "ADJ_1") (pintype "bidirectional"))
    )
    (net (code "56") (name "VDD_AMP") (class "Default")
      (node (ref "C54") (pin "1") (pinfunction "1_1") (pintype "bidirectional"))
      (node (ref "C55") (pin "2") (pinfunction "A_2") (pintype "bidirectional"))
      (node (ref "C56") (pin "1") (pinfunction "1_1") (pintype "bidirectional"))
      (node (ref "HOLE5") (pin "1") (pinfunction "1_1") (pintype "bidirectional"))
      (node (ref "R6") (pin "1") (pinfunction "1_1") (pintype "bidirectional"))
      (node (ref "U2") (pin "1") (pinfunction "VIN_1") (pintype "bidirectional"))
      (node (ref "U4") (pin "29") (pinfunction "PVDD_CD_29") (pintype "bidirectional"))
      (node (ref "U4") (pin "30") (pinfunction "PVDD_CD_30") (pintype "bidirectional"))
      (node (ref "U4") (pin "31") (pinfunction "PVDD_CD_31") (pintype "bidirectional"))
      (node (ref "U4") (pin "36") (pinfunction "PVDD_AB_36") (pintype "bidirectional"))
      (node (ref "U4") (pin "37") (pinfunction "PVDD_AB_37") (pintype "bidirectional"))
      (node (ref "U4") (pin "38") (pinfunction "PVDD_AB_38") (pintype "bidirectional"))
    )
    (net (code "57") (name "unconnected-(CN7-SWO-Pad6)") (class "Default")
      (node (ref "CN7") (pin "6") (pinfunction "SWO_6") (pintype "output"))
    )
    (net (code "58") (name "unconnected-(RL1B-2-Pad12)") (class "Default")
      (node (ref "RL1") (pin "12") (pinfunction "2_12") (pintype "bidirectional"))
    )
    (net (code "59") (name "unconnected-(RL1C-2-Pad22)") (class "Default")
      (node (ref "RL1") (pin "22") (pinfunction "2_22") (pintype "bidirectional"))
    )
    (net (code "60") (name "unconnected-(RL2B-2-Pad12)") (class "Default")
      (node (ref "RL2") (pin "12") (pinfunction "2_12") (pintype "bidirectional"))
    )
    (net (code "61") (name "unconnected-(RL2C-2-Pad22)") (class "Default")
      (node (ref "RL2") (pin "22") (pinfunction "2_22") (pintype "bidirectional"))
    )
    (net (code "62") (name "unconnected-(U1-PA4-Pad10)") (class "Default")
      (node (ref "U1") (pin "10") (pinfunction "PA4_10") (pintype "bidirectional"))
    )
    (net (code "63") (name "unconnected-(U1-PA5-Pad11)") (class "Default")
      (node (ref "U1") (pin "11") (pinfunction "PA5_11") (pintype "bidirectional"))
    )
    (net (code "64") (name "unconnected-(U1-PA6-Pad12)") (class "Default")
      (node (ref "U1") (pin "12") (pinfunction "PA6_12") (pintype "bidirectional"))
    )
    (net (code "65") (name "unconnected-(U1-PA7-Pad13)") (class "Default")
      (node (ref "U1") (pin "13") (pinfunction "PA7_13") (pintype "bidirectional"))
    )
    (net (code "66") (name "unconnected-(U1-PA8-Pad18)") (class "Default")
      (node (ref "U1") (pin "18") (pinfunction "PA8_18") (pintype "bidirectional"))
    )
    (net (code "67") (name "unconnected-(U1-PA9-Pad19)") (class "Default")
      (node (ref "U1") (pin "19") (pinfunction "PA9_19") (pintype "bidirectional"))
    )
    (net (code "68") (name "unconnected-(U1-PA10-Pad20)") (class "Default")
      (node (ref "U1") (pin "20") (pinfunction "PA10_20") (pintype "bidirectional"))
    )
    (net (code "69") (name "unconnected-(U1-PB0-Pad14)") (class "Default")
      (node (ref "U1") (pin "14") (pinfunction "PB0_14") (pintype "bidirectional"))
    )
    (net (code "70") (name "unconnected-(U1-PB1-Pad15)") (class "Default")
      (node (ref "U1") (pin "15") (pinfunction "PB1_15") (pintype "bidirectional"))
    )
    (net (code "71") (name "unconnected-(U1-PB6-Pad25)") (class "Default")
      (node (ref "U1") (pin "25") (pinfunction "PB6_25") (pintype "bidirectional"))
    )
    (net (code "72") (name "unconnected-(U1-PB7-Pad26)") (class "Default")
      (node (ref "U1") (pin "26") (pinfunction "PB7_26") (pintype "bidirectional"))
    )
    (net (code "73") (name "unconnected-(U4-OSC_IOM-Pad9)") (class "Default")
      (node (ref "U4") (pin "9") (pinfunction "OSC_IOM_9") (pintype "bidirectional"))
    )
    (net (code "74") (name "unconnected-(U4-OSC_IOP-Pad10)") (class "Default")
      (node (ref "U4") (pin "10") (pinfunction "OSC_IOP_10") (pintype "bidirectional"))
    )
  )
)
